# Schematic.net
KiCad netlist of a schematic drawn in EAGLE
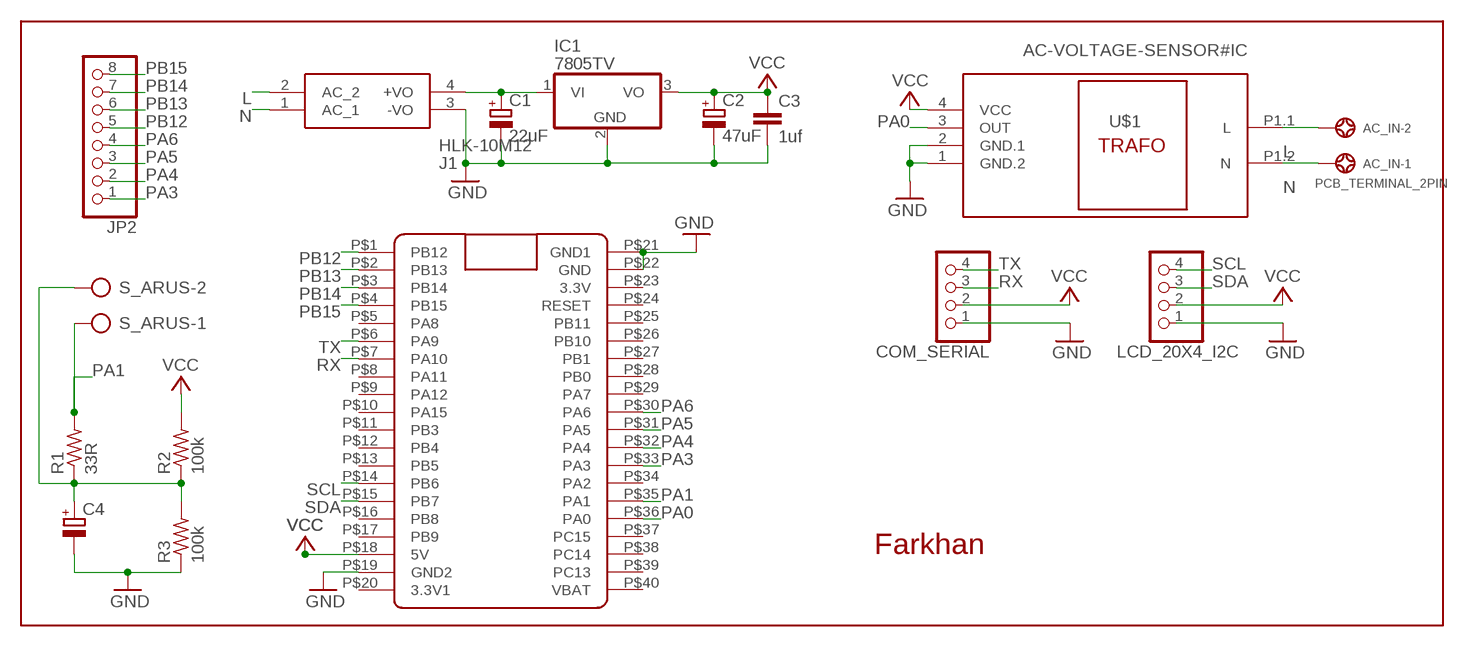
[diagram p0: schematic, sheet 1]

(export (version "E")
  (design (tool "Eeschema 10.0.6"))
  (components
    (comp (ref "AC_IN")
      (value "PCB_TERMINAL_2PIN")
      (footprint "eagle-import:PCB_TERMINAL_2PIN")
      (libsource (lib "eagle-import") (part "PCB_TERMINAL_2PIN"))
    )
    (comp (ref "C1")
      (value "22uF")
      (footprint "eagle-import:E2,5-7")
      (libsource (lib "eagle-import") (part "CPOL-EUE2.5-7"))
    )
    (comp (ref "C2")
      (value "47uF")
      (footprint "eagle-import:E2,5-7")
      (libsource (lib "eagle-import") (part "CPOL-EUE2.5-7"))
    )
    (comp (ref "C3")
      (value "1uf")
      (footprint "eagle-import:C050-025X075")
      (libsource (lib "eagle-import") (part "C-EU050-025X075"))
    )
    (comp (ref "C4")
      (value "CPOL-EUE2.5-6")
      (footprint "eagle-import:E2,5-6")
      (libsource (lib "eagle-import") (part "CPOL-EUE2.5-6"))
    )
    (comp (ref "COM_SERIAL")
      (value "PINHD-1X4")
      (footprint "eagle-import:1X04")
      (libsource (lib "eagle-import") (part "PINHD-1X4"))
    )
    (comp (ref "IC1")
      (value "7805TV")
      (footprint "eagle-import:TO220V")
      (libsource (lib "eagle-import") (part "78TV05"))
    )
    (comp (ref "J1")
      (value "HLK-10M12")
      (footprint "eagle-import:HLK10M12")
      (libsource (lib "eagle-import") (part "HLK-10M12"))
    )
    (comp (ref "JP2")
      (value "PINHD-1X8")
      (footprint "eagle-import:1X08")
      (libsource (lib "eagle-import") (part "PINHD-1X8"))
    )
    (comp (ref "LCD_20X4_I2C")
      (value "PINHD-1X4")
      (footprint "eagle-import:1X04")
      (libsource (lib "eagle-import") (part "PINHD-1X4"))
    )
    (comp (ref "R1")
      (value "33R")
      (footprint "eagle-import:0207_10")
      (libsource (lib "eagle-import") (part "R-US_0207/10"))
    )
    (comp (ref "R2")
      (value "100k")
      (footprint "eagle-import:0207_10")
      (libsource (lib "eagle-import") (part "R-US_0207/10"))
    )
    (comp (ref "R3")
      (value "100k")
      (footprint "eagle-import:0207_10")
      (libsource (lib "eagle-import") (part "R-US_0207/10"))
    )
    (comp (ref "S_ARUS")
      (value "AK500/2")
      (footprint "eagle-import:AK500_2")
      (libsource (lib "eagle-import") (part "AK500/2"))
    )
    (comp (ref "U$1")
      (value "AC-VOLTAGE-SENSOR#IC")
      (footprint "eagle-import:AC-VOLTAGE-SENSOR#IC")
      (libsource (lib "eagle-import") (part "AC-VOLTAGE-SENSOR#IC"))
    )
    (comp (ref "U$2")
      (value "BLUE_PILL")
      (footprint "eagle-import:BLUE_PILL")
      (libsource (lib "eagle-import") (part "BLUE_PILL"))
    )
  )
  (nets
    (net (code "1") (name "/L") (class "Default")
      (node (ref "AC_IN") (pin "2") (pinfunction "1_2") (pintype "passive"))
      (node (ref "J1") (pin "2") (pinfunction "AC_2_2") (pintype "bidirectional"))
      (node (ref "U$1") (pin "P1.1") (pinfunction "L_P1.1") (pintype "passive"))
    )
    (net (code "2") (name "/N") (class "Default")
      (node (ref "AC_IN") (pin "1") (pinfunction "1_1") (pintype "passive"))
      (node (ref "J1") (pin "1") (pinfunction "AC_1_1") (pintype "bidirectional"))
      (node (ref "U$1") (pin "P1.2") (pinfunction "N_P1.2") (pintype "passive"))
    )
    (net (code "3") (name "/PA0") (class "Default")
      (node (ref "U$1") (pin "3") (pinfunction "OUT_3") (pintype "output"))
      (node (ref "U$2") (pin "P$36") (pinfunction "PA0_P$36") (pintype "bidirectional"))
    )
    (net (code "4") (name "/PA1") (class "Default")
      (node (ref "R1") (pin "2") (pinfunction "2_2") (pintype "passive"))
      (node (ref "S_ARUS") (pin "1") (pinfunction "KL_1") (pintype "passive"))
      (node (ref "U$2") (pin "P$35") (pinfunction "PA1_P$35") (pintype "bidirectional"))
    )
    (net (code "5") (name "/PA3") (class "Default")
      (node (ref "JP2") (pin "1") (pinfunction "1_1") (pintype "passive"))
      (node (ref "U$2") (pin "P$33") (pinfunction "PA3_P$33") (pintype "bidirectional"))
    )
    (net (code "6") (name "/PA4") (class "Default")
      (node (ref "JP2") (pin "2") (pinfunction "2_2") (pintype "passive"))
      (node (ref "U$2") (pin "P$32") (pinfunction "PA4_P$32") (pintype "bidirectional"))
    )
    (net (code "7") (name "/PA5") (class "Default")
      (node (ref "JP2") (pin "3") (pinfunction "3_3") (pintype "passive"))
      (node (ref "U$2") (pin "P$31") (pinfunction "PA5_P$31") (pintype "bidirectional"))
    )
    (net (code "8") (name "/PA6") (class "Default")
      (node (ref "JP2") (pin "4") (pinfunction "4_4") (pintype "passive"))
      (node (ref "U$2") (pin "P$30") (pinfunction "PA6_P$30") (pintype "bidirectional"))
    )
    (net (code "9") (name "/PB12") (class "Default")
      (node (ref "JP2") (pin "5") (pinfunction "5_5") (pintype "passive"))
      (node (ref "U$2") (pin "P$1") (pinfunction "PB12_P$1") (pintype "bidirectional"))
    )
    (net (code "10") (name "/PB13") (class "Default")
      (node (ref "JP2") (pin "6") (pinfunction "6_6") (pintype "passive"))
      (node (ref "U$2") (pin "P$2") (pinfunction "PB13_P$2") (pintype "bidirectional"))
    )
    (net (code "11") (name "/PB14") (class "Default")
      (node (ref "JP2") (pin "7") (pinfunction "7_7") (pintype "passive"))
      (node (ref "U$2") (pin "P$3") (pinfunction "PB14_P$3") (pintype "bidirectional"))
    )
    (net (code "12") (name "/PB15") (class "Default")
      (node (ref "JP2") (pin "8") (pinfunction "8_8") (pintype "passive"))
      (node (ref "U$2") (pin "P$4") (pinfunction "PB15_P$4") (pintype "bidirectional"))
    )
    (net (code "13") (name "/RX") (class "Default")
      (node (ref "COM_SERIAL") (pin "3") (pinfunction "3_3") (pintype "passive"))
      (node (ref "U$2") (pin "P$7") (pinfunction "PA10_P$7") (pintype "bidirectional"))
    )
    (net (code "14") (name "/SCL") (class "Default")
      (node (ref "LCD_20X4_I2C") (pin "4") (pinfunction "4_4") (pintype "passive"))
      (node (ref "U$2") (pin "P$14") (pinfunction "PB6_P$14") (pintype "bidirectional"))
    )
    (net (code "15") (name "/SDA") (class "Default")
      (node (ref "LCD_20X4_I2C") (pin "3") (pinfunction "3_3") (pintype "passive"))
      (node (ref "U$2") (pin "P$15") (pinfunction "PB7_P$15") (pintype "bidirectional"))
    )
    (net (code "16") (name "/TX") (class "Default")
      (node (ref "COM_SERIAL") (pin "4") (pinfunction "4_4") (pintype "passive"))
      (node (ref "U$2") (pin "P$6") (pinfunction "PA9_P$6") (pintype "bidirectional"))
    )
    (net (code "17") (name "GND") (class "Default")
      (node (ref "C1") (pin "-") (pinfunction "-_-") (pintype "passive"))
      (node (ref "C2") (pin "-") (pinfunction "-_-") (pintype "passive"))
      (node (ref "C3") (pin "2") (pinfunction "2_2") (pintype "passive"))
      (node (ref "C4") (pin "-") (pinfunction "-_-") (pintype "passive"))
      (node (ref "COM_SERIAL") (pin "1") (pinfunction "1_1") (pintype "passive"))
      (node (ref "IC1") (pin "2") (pinfunction "GND_2") (pintype "passive"))
      (node (ref "J1") (pin "3") (pinfunction "-VO_3") (pintype "bidirectional"))
      (node (ref "LCD_20X4_I2C") (pin "1") (pinfunction "1_1") (pintype "passive"))
      (node (ref "R3") (pin "1") (pinfunction "1_1") (pintype "passive"))
      (node (ref "U$1") (pin "1") (pinfunction "GND.2_1") (pintype "power_in"))
      (node (ref "U$1") (pin "2") (pinfunction "GND.1_2") (pintype "power_in"))
      (node (ref "U$2") (pin "P$19") (pinfunction "GND2_P$19") (pintype "bidirectional"))
      (node (ref "U$2") (pin "P$21") (pinfunction "GND1_P$21") (pintype "power_in"))
      (node (ref "U$2") (pin "P$22") (pinfunction "GND_P$22") (pintype "bidirectional"))
    )
    (net (code "18") (name "Net-(IC1-VI)") (class "Default")
      (node (ref "C1") (pin "+") (pinfunction "+_+") (pintype "passive"))
      (node (ref "IC1") (pin "1") (pinfunction "VI_1") (pintype "input"))
      (node (ref "J1") (pin "4") (pinfunction "+VO_4") (pintype "bidirectional"))
    )
    (net (code "19") (name "Net-(S_ARUSB-KL)") (class "Default")
      (node (ref "C4") (pin "+") (pinfunction "+_+") (pintype "passive"))
      (node (ref "R1") (pin "1") (pinfunction "1_1") (pintype "passive"))
      (node (ref "R2") (pin "1") (pinfunction "1_1") (pintype "passive"))
      (node (ref "R3") (pin "2") (pinfunction "2_2") (pintype "passive"))
      (node (ref "S_ARUS") (pin "2") (pinfunction "KL_2") (pintype "passive"))
    )
    (net (code "20") (name "VCC") (class "Default")
      (node (ref "C2") (pin "+") (pinfunction "+_+") (pintype "passive"))
      (node (ref "C3") (pin "1") (pinfunction "1_1") (pintype "passive"))
      (node (ref "COM_SERIAL") (pin "2") (pinfunction "2_2") (pintype "passive"))
      (node (ref "IC1") (pin "3") (pinfunction "VO_3") (pintype "passive"))
      (node (ref "LCD_20X4_I2C") (pin "2") (pinfunction "2_2") (pintype "passive"))
      (node (ref "R2") (pin "2") (pinfunction "2_2") (pintype "passive"))
      (node (ref "U$1") (pin "4") (pinfunction "VCC_4") (pintype "power_in"))
      (node (ref "U$2") (pin "P$18") (pinfunction "5V_P$18") (pintype "bidirectional"))
    )
    (net (code "21") (name "unconnected-(U$2-3.3V-PadP$23)") (class "Default")
      (node (ref "U$2") (pin "P$23") (pinfunction "3.3V_P$23") (pintype "bidirectional"))
    )
    (net (code "22") (name "unconnected-(U$2-3.3V1-PadP$20)") (class "Default")
      (node (ref "U$2") (pin "P$20") (pinfunction "3.3V1_P$20") (pintype "bidirectional"))
    )
    (net (code "23") (name "unconnected-(U$2-PA2-PadP$34)") (class "Default")
      (node (ref "U$2") (pin "P$34") (pinfunction "PA2_P$34") (pintype "bidirectional"))
    )
    (net (code "24") (name "unconnected-(U$2-PA7-PadP$29)") (class "Default")
      (node (ref "U$2") (pin "P$29") (pinfunction "PA7_P$29") (pintype "bidirectional"))
    )
    (net (code "25") (name "unconnected-(U$2-PA8-PadP$5)") (class "Default")
      (node (ref "U$2") (pin "P$5") (pinfunction "PA8_P$5") (pintype "bidirectional"))
    )
    (net (code "26") (name "unconnected-(U$2-PA11-PadP$8)") (class "Default")
      (node (ref "U$2") (pin "P$8") (pinfunction "PA11_P$8") (pintype "bidirectional"))
    )
    (net (code "27") (name "unconnected-(U$2-PA12-PadP$9)") (class "Default")
      (node (ref "U$2") (pin "P$9") (pinfunction "PA12_P$9") (pintype "bidirectional"))
    )
    (net (code "28") (name "unconnected-(U$2-PA15-PadP$10)") (class "Default")
      (node (ref "U$2") (pin "P$10") (pinfunction "PA15_P$10") (pintype "bidirectional"))
    )
    (net (code "29") (name "unconnected-(U$2-PB0-PadP$28)") (class "Default")
      (node (ref "U$2") (pin "P$28") (pinfunction "PB0_P$28") (pintype "bidirectional"))
    )
    (net (code "30") (name "unconnected-(U$2-PB1-PadP$27)") (class "Default")
      (node (ref "U$2") (pin "P$27") (pinfunction "PB1_P$27") (pintype "bidirectional"))
    )
    (net (code "31") (name "unconnected-(U$2-PB3-PadP$11)") (class "Default")
      (node (ref "U$2") (pin "P$11") (pinfunction "PB3_P$11") (pintype "bidirectional"))
    )
    (net (code "32") (name "unconnected-(U$2-PB4-PadP$12)") (class "Default")
      (node (ref "U$2") (pin "P$12") (pinfunction "PB4_P$12") (pintype "bidirectional"))
    )
    (net (code "33") (name "unconnected-(U$2-PB5-PadP$13)") (class "Default")
      (node (ref "U$2") (pin "P$13") (pinfunction "PB5_P$13") (pintype "bidirectional"))
    )
    (net (code "34") (name "unconnected-(U$2-PB8-PadP$16)") (class "Default")
      (node (ref "U$2") (pin "P$16") (pinfunction "PB8_P$16") (pintype "bidirectional"))
    )
    (net (code "35") (name "unconnected-(U$2-PB9-PadP$17)") (class "Default")
      (node (ref "U$2") (pin "P$17") (pinfunction "PB9_P$17") (pintype "bidirectional"))
    )
    (net (code "36") (name "unconnected-(U$2-PB10-PadP$26)") (class "Default")
      (node (ref "U$2") (pin "P$26") (pinfunction "PB10_P$26") (pintype "bidirectional"))
    )
    (net (code "37") (name "unconnected-(U$2-PB11-PadP$25)") (class "Default")
      (node (ref "U$2") (pin "P$25") (pinfunction "PB11_P$25") (pintype "bidirectional"))
    )
    (net (code "38") (name "unconnected-(U$2-PC13-PadP$39)") (class "Default")
      (node (ref "U$2") (pin "P$39") (pinfunction "PC13_P$39") (pintype "bidirectional"))
    )
    (net (code "39") (name "unconnected-(U$2-PC14-PadP$38)") (class "Default")
      (node (ref "U$2") (pin "P$38") (pinfunction "PC14_P$38") (pintype "bidirectional"))
    )
    (net (code "40") (name "unconnected-(U$2-PC15-PadP$37)") (class "Default")
      (node (ref "U$2") (pin "P$37") (pinfunction "PC15_P$37") (pintype "bidirectional"))
    )
    (net (code "41") (name "unconnected-(U$2-RESET-PadP$24)") (class "Default")
      (node (ref "U$2") (pin "P$24") (pinfunction "RESET_P$24") (pintype "bidirectional"))
    )
    (net (code "42") (name "unconnected-(U$2-VBAT-PadP$40)") (class "Default")
      (node (ref "U$2") (pin "P$40") (pinfunction "VBAT_P$40") (pintype "bidirectional"))
    )
  )
)
